# Precharge_M2019_V1_0.net
KiCad netlist of a schematic drawn in EAGLE
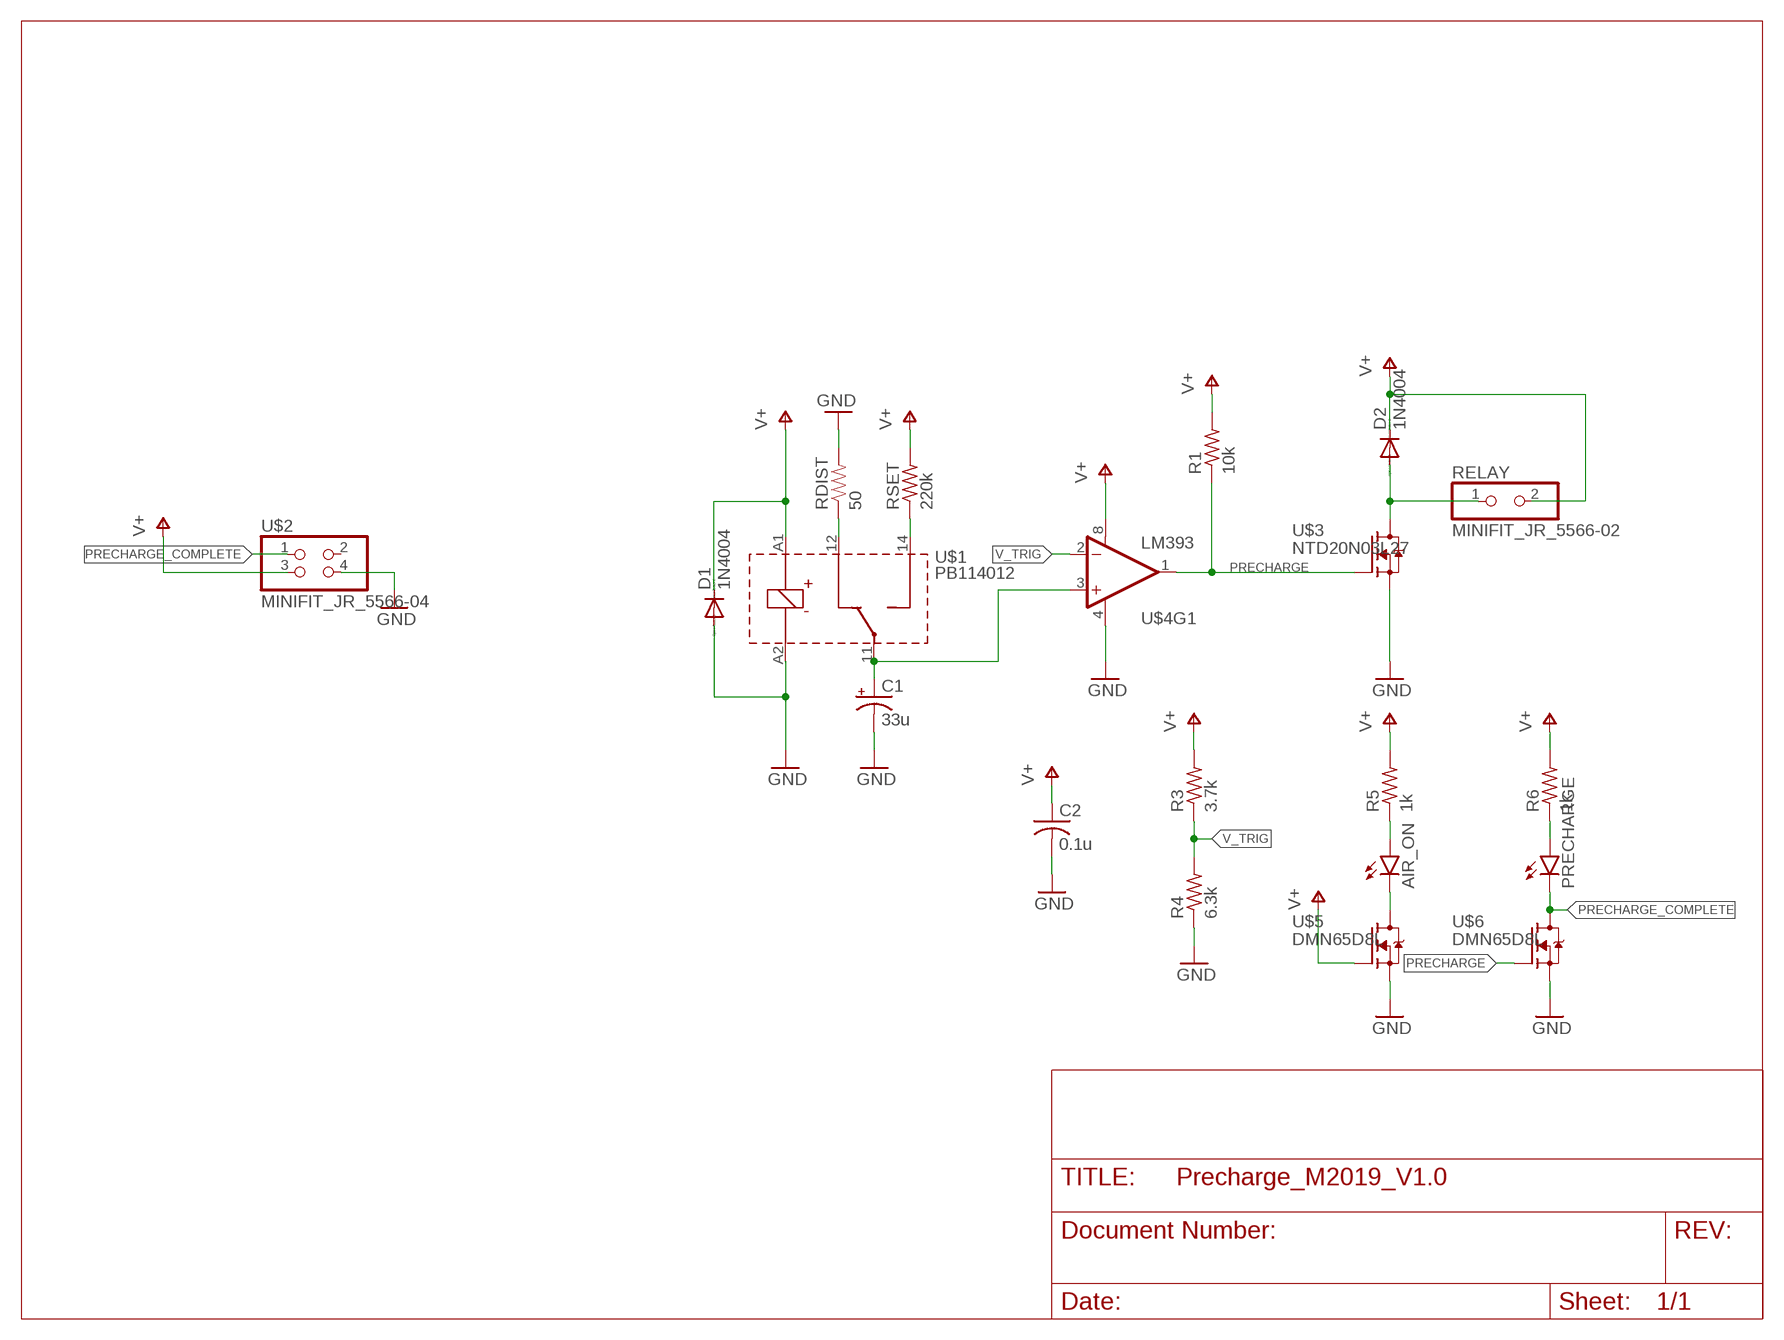
[diagram p0: schematic, sheet 1]

(export (version "E")
  (design (tool "Eeschema 10.0.6"))
  (components
    (comp (ref "AIR_ON")
      (value "LED0603")
      (footprint "eagle-import:LED-0603")
      (libsource (lib "eagle-import") (part "LED0603"))
    )
    (comp (ref "C1")
      (value "33u")
      (footprint "eagle-import:E2,5-5")
      (libsource (lib "eagle-import") (part "CPOL-USE2.5-5"))
    )
    (comp (ref "C2")
      (value "0.1u")
      (footprint "eagle-import:C0805")
      (libsource (lib "eagle-import") (part "C-USC0805"))
    )
    (comp (ref "D1")
      (value "1N4004")
      (footprint "eagle-import:DO41-10")
      (libsource (lib "eagle-import") (part "1N4004"))
    )
    (comp (ref "D2")
      (value "1N4004")
      (footprint "eagle-import:DO41-10")
      (libsource (lib "eagle-import") (part "1N4004"))
    )
    (comp (ref "PRECHARGE")
      (value "LED0603")
      (footprint "eagle-import:LED-0603")
      (libsource (lib "eagle-import") (part "LED0603"))
    )
    (comp (ref "R1")
      (value "10k")
      (footprint "eagle-import:R0805")
      (libsource (lib "eagle-import") (part "R-US_R0805"))
    )
    (comp (ref "R3")
      (value "3.7k")
      (footprint "eagle-import:R0805")
      (libsource (lib "eagle-import") (part "R-US_R0805"))
    )
    (comp (ref "R4")
      (value "6.3k")
      (footprint "eagle-import:R0805")
      (libsource (lib "eagle-import") (part "R-US_R0805"))
    )
    (comp (ref "R5")
      (value "1k")
      (footprint "eagle-import:R0805")
      (libsource (lib "eagle-import") (part "R-US_R0805"))
    )
    (comp (ref "R6")
      (value "1k")
      (footprint "eagle-import:R0805")
      (libsource (lib "eagle-import") (part "R-US_R0805"))
    )
    (comp (ref "RDIST")
      (value "50")
      (footprint "eagle-import:AXIAL-0.5")
      (libsource (lib "eagle-import") (part "RESISTORPTH-1/2W"))
    )
    (comp (ref "RELAY")
      (value "MINIFIT_JR_5566-02")
      (footprint "eagle-import:MINIFIT_JR_5566-02")
      (libsource (lib "eagle-import") (part "MINIFIT_JR_5566-02"))
    )
    (comp (ref "RSET")
      (value "220k")
      (footprint "eagle-import:0207_10")
      (libsource (lib "eagle-import") (part "R-US_0207/10"))
    )
    (comp (ref "U$1")
      (value "PB114012")
      (footprint "eagle-import:TH_SPDT_MINI_POWER_RELAY_PB")
      (libsource (lib "eagle-import") (part "PB114012"))
    )
    (comp (ref "U$2")
      (value "MINIFIT_JR_5566-04")
      (footprint "eagle-import:MINIFIT_JR_5566-04")
      (libsource (lib "eagle-import") (part "MINIFIT_JR_5566-04"))
    )
    (comp (ref "U$3")
      (value "NTD20N03L27")
      (footprint "eagle-import:DPACK")
      (libsource (lib "eagle-import") (part "NTD20N03L27"))
    )
    (comp (ref "U$4")
      (value "LM393")
      (footprint "eagle-import:SO08")
      (libsource (lib "eagle-import") (part "LM393"))
    )
    (comp (ref "U$5")
      (value "DMN65D8L")
      (footprint "eagle-import:SOT23")
      (libsource (lib "eagle-import") (part "DMN65D8L"))
    )
    (comp (ref "U$6")
      (value "DMN65D8L")
      (footprint "eagle-import:SOT23")
      (libsource (lib "eagle-import") (part "DMN65D8L"))
    )
  )
  (nets
    (net (code "1") (name "GND") (class "Default")
      (node (ref "C1") (pin "-") (pinfunction "-_-") (pintype "passive"))
      (node (ref "C2") (pin "2") (pinfunction "2_2") (pintype "passive"))
      (node (ref "D1") (pin "A") (pinfunction "A_A") (pintype "passive"))
      (node (ref "R4") (pin "1") (pinfunction "1_1") (pintype "passive"))
      (node (ref "RDIST") (pin "P$2") (pinfunction "2_P$2") (pintype "passive"))
      (node (ref "U$1") (pin "A2") (pinfunction "COIL-_A2") (pintype "bidirectional"))
      (node (ref "U$2") (pin "4") (pinfunction "4_4") (pintype "passive"))
      (node (ref "U$3") (pin "3") (pinfunction "S_3") (pintype "passive"))
      (node (ref "U$4") (pin "4") (pinfunction "V-_4") (pintype "power_in"))
      (node (ref "U$5") (pin "2") (pinfunction "S_2") (pintype "passive"))
      (node (ref "U$6") (pin "2") (pinfunction "S_2") (pintype "passive"))
    )
    (net (code "2") (name "Net-(AIR_ON-PadA)") (class "Default")
      (node (ref "AIR_ON") (pin "A") (pinfunction "A_A") (pintype "passive"))
      (node (ref "R5") (pin "1") (pinfunction "1_1") (pintype "passive"))
    )
    (net (code "3") (name "Net-(PRECHARGE-PadA)") (class "Default")
      (node (ref "PRECHARGE") (pin "A") (pinfunction "A_A") (pintype "passive"))
      (node (ref "R6") (pin "1") (pinfunction "1_1") (pintype "passive"))
    )
    (net (code "4") (name "Net-(RDIST-1)") (class "Default")
      (node (ref "RDIST") (pin "P$1") (pinfunction "1_P$1") (pintype "passive"))
      (node (ref "U$1") (pin "12") (pinfunction "NC_12") (pintype "passive"))
    )
    (net (code "5") (name "Net-(U$1-COM)") (class "Default")
      (node (ref "C1") (pin "+") (pinfunction "+_+") (pintype "passive"))
      (node (ref "U$1") (pin "11") (pinfunction "COM_11") (pintype "passive"))
      (node (ref "U$4") (pin "3") (pinfunction "+IN_3") (pintype "input"))
    )
    (net (code "6") (name "Net-(U$1-NO)") (class "Default")
      (node (ref "RSET") (pin "1") (pinfunction "1_1") (pintype "passive"))
      (node (ref "U$1") (pin "14") (pinfunction "NO_14") (pintype "passive"))
    )
    (net (code "7") (name "Net-(U$3-D)") (class "Default")
      (node (ref "D2") (pin "A") (pinfunction "A_A") (pintype "passive"))
      (node (ref "RELAY") (pin "1") (pinfunction "1_1") (pintype "passive"))
      (node (ref "U$3") (pin "2") (pinfunction "D_2") (pintype "passive"))
    )
    (net (code "8") (name "Net-(U$5-D)") (class "Default")
      (node (ref "AIR_ON") (pin "C") (pinfunction "C_C") (pintype "passive"))
      (node (ref "U$5") (pin "3") (pinfunction "D_3") (pintype "passive"))
    )
    (net (code "9") (name "PRECHARGE") (class "Default")
      (node (ref "R1") (pin "1") (pinfunction "1_1") (pintype "passive"))
      (node (ref "U$3") (pin "1") (pinfunction "G_1") (pintype "passive"))
      (node (ref "U$4") (pin "1") (pinfunction "OUT_1") (pintype "output"))
      (node (ref "U$6") (pin "1") (pinfunction "G_1") (pintype "passive"))
    )
    (net (code "10") (name "PRECHARGE_COMPLETE") (class "Default")
      (node (ref "PRECHARGE") (pin "C") (pinfunction "C_C") (pintype "passive"))
      (node (ref "U$2") (pin "1") (pinfunction "1_1") (pintype "passive"))
      (node (ref "U$6") (pin "3") (pinfunction "D_3") (pintype "passive"))
    )
    (net (code "11") (name "V+") (class "Default")
      (node (ref "C2") (pin "1") (pinfunction "1_1") (pintype "passive"))
      (node (ref "D1") (pin "C") (pinfunction "C_C") (pintype "passive"))
      (node (ref "D2") (pin "C") (pinfunction "C_C") (pintype "passive"))
      (node (ref "R1") (pin "2") (pinfunction "2_2") (pintype "passive"))
      (node (ref "R3") (pin "2") (pinfunction "2_2") (pintype "passive"))
      (node (ref "R5") (pin "2") (pinfunction "2_2") (pintype "passive"))
      (node (ref "R6") (pin "2") (pinfunction "2_2") (pintype "passive"))
      (node (ref "RELAY") (pin "2") (pinfunction "2_2") (pintype "passive"))
      (node (ref "RSET") (pin "2") (pinfunction "2_2") (pintype "passive"))
      (node (ref "U$1") (pin "A1") (pinfunction "COIL+_A1") (pintype "bidirectional"))
      (node (ref "U$2") (pin "3") (pinfunction "3_3") (pintype "passive"))
      (node (ref "U$4") (pin "8") (pinfunction "V+_8") (pintype "power_in"))
      (node (ref "U$5") (pin "1") (pinfunction "G_1") (pintype "passive"))
    )
    (net (code "12") (name "V_TRIG") (class "Default")
      (node (ref "R3") (pin "1") (pinfunction "1_1") (pintype "passive"))
      (node (ref "R4") (pin "2") (pinfunction "2_2") (pintype "passive"))
      (node (ref "U$4") (pin "2") (pinfunction "-IN_2") (pintype "input"))
    )
    (net (code "13") (name "unconnected-(U$2-Pad2)") (class "Default")
      (node (ref "U$2") (pin "2") (pinfunction "2_2") (pintype "passive"))
    )
  )
)
